# 48-17V_Buck_Converter.net
KiCad netlist of a schematic drawn in Altium Designer
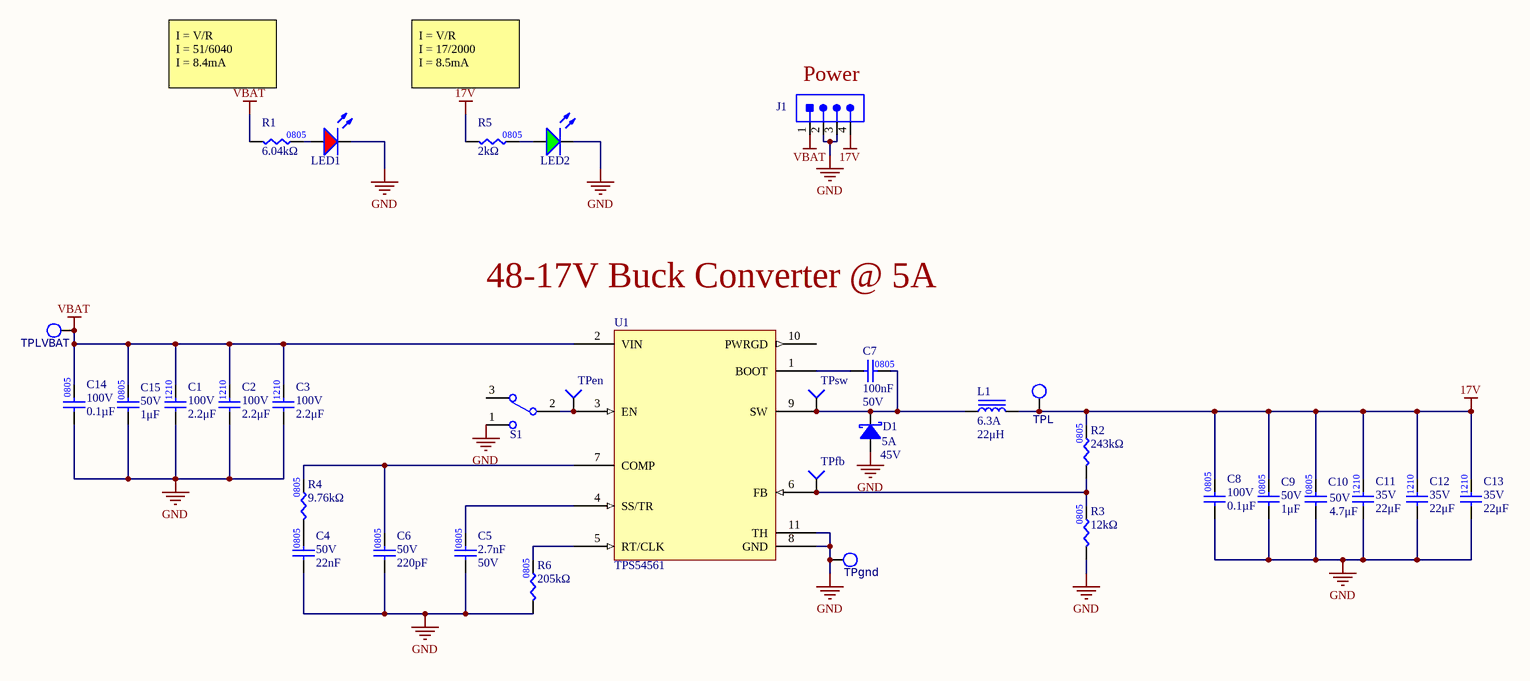
[diagram p0: 48-17V Buck Converter.SchDoc]

(export (version "E")
  (design (tool "Eeschema 10.0.6"))
  (components
    (comp (ref "C1")
      (value "2.2μF")
      (footprint "CAPC3225X270N")
      (description "CAP CER 2.2UF 100V X7R 1210")
      (fields (field (name "VOLTAGE RATING") "100V") (field (name "Comment") "CAP_2.2uF_100V_1210_1"))
      (libsource (lib "UWRT_Schematic_Library_2020") (part "CAP_2.2uF_100V_1210_1"))
    )
    (comp (ref "C2")
      (value "2.2μF")
      (footprint "CAPC3225X270N")
      (description "CAP CER 2.2UF 100V X7R 1210")
      (fields (field (name "VOLTAGE RATING") "100V") (field (name "Comment") "CAP_2.2uF_100V_1210_1"))
      (libsource (lib "UWRT_Schematic_Library_2020") (part "CAP_2.2uF_100V_1210_1"))
    )
    (comp (ref "C3")
      (value "2.2μF")
      (footprint "CAPC3225X270N")
      (description "CAP CER 2.2UF 100V X7R 1210")
      (fields (field (name "VOLTAGE RATING") "100V") (field (name "Comment") "CAP_2.2uF_100V_1210_1"))
      (libsource (lib "UWRT_Schematic_Library_2020") (part "CAP_2.2uF_100V_1210_1"))
    )
    (comp (ref "C4")
      (value "22nF")
      (footprint "CAP2012")
      (description "CAP CER 22nF 50V 0805")
      (fields (field (name "VOLTAGE RATING") "50V") (field (name "Comment") "CAP_22nF_50V_0805 +/- 1%"))
      (libsource (lib "UWRT_Schematic_Library_2020") (part "CAP_22nF_50V_0805 +/- 1%"))
    )
    (comp (ref "C5")
      (value "2.7nF")
      (footprint "CAP0805")
      (description "CAP CER 2700PF 50V C0G 0805")
      (fields (field (name "VOLTAGE RATING") "50V") (field (name "Comment") "CAP_2.7nF_50V_0805"))
      (libsource (lib "UWRT_Schematic_Library_2020") (part "CAP_2.7nF_50V_0805"))
    )
    (comp (ref "C6")
      (value "220pF")
      (footprint "CAP2012")
      (description "CAP CER 220pF 50V 0805 +/-1%")
      (fields (field (name "VOLTAGE RATING") "50V") (field (name "Comment") "CAP_220pF_50V_0805_2_1"))
      (libsource (lib "UWRT_Schematic_Library_2020") (part "CAP_220pF_50V_0805_2_1"))
    )
    (comp (ref "C7")
      (value "100nF")
      (footprint "CAP0805")
      (description "CAP CER 0.1UF 50V X7R 0805")
      (fields (field (name "VOLTAGE RATING") "50V") (field (name "Comment") "CAP_100nF_50V_0805"))
      (libsource (lib "UWRT_Schematic_Library_2020") (part "CAP_100nF_50V_0805"))
    )
    (comp (ref "C8")
      (value "0.1µF")
      (footprint "CAP0805")
      (description "CAP CER 0.1UF 100V X7R 0805")
      (fields (field (name "VOLTAGE RATING") "100V") (field (name "Comment") "CAP_0.1uF_100V_0805"))
      (libsource (lib "UWRT_Schematic_Library_2020") (part "CAP_0.1uF_100V_0805"))
    )
    (comp (ref "C9")
      (value "1μF")
      (footprint "CAP2012")
      (description "CAP CER 1UF 50V X7R 0805")
      (fields
        (field (name "LCSC PART #") "C28323")
        (field (name "VOLTAGE RATING") "50V")
        (field (name "Comment") "CAP_1uF_50V_0805")
      )
      (libsource (lib "UWRT_Schematic_Library_2020") (part "CAP_1uF_50V_0805"))
    )
    (comp (ref "C10")
      (value "4.7μF")
      (footprint "CAP0805")
      (description "CAP CER 4.7UF 50V X5R 0805")
      (fields
        (field (name "LCSC PART #") "C1779")
        (field (name "VOLTAGE RATING") "50V")
        (field (name "Comment") "CAP_4.7uF_50V_0805")
      )
      (libsource (lib "UWRT_Schematic_Library_2020") (part "CAP_4.7uF_50V_0805"))
    )
    (comp (ref "C11")
      (value "22μF")
      (footprint "CAP1210")
      (description "CAP CER 22UF 35V X5R 1210")
      (fields (field (name "VOLTAGE RATING") "35V") (field (name "Comment") "CAP_22uF_100V_1210"))
      (libsource (lib "UWRT_Schematic_Library_2020") (part "CAP_22uF_100V_1210"))
    )
    (comp (ref "C12")
      (value "22μF")
      (footprint "CAP1210")
      (description "CAP CER 22UF 35V X5R 1210")
      (fields (field (name "VOLTAGE RATING") "35V") (field (name "Comment") "CAP_22uF_100V_1210"))
      (libsource (lib "UWRT_Schematic_Library_2020") (part "CAP_22uF_100V_1210"))
    )
    (comp (ref "C13")
      (value "22μF")
      (footprint "CAP1210")
      (description "CAP CER 22UF 35V X5R 1210")
      (fields (field (name "VOLTAGE RATING") "35V") (field (name "Comment") "CAP_22uF_100V_1210"))
      (libsource (lib "UWRT_Schematic_Library_2020") (part "CAP_22uF_100V_1210"))
    )
    (comp (ref "C14")
      (value "0.1µF")
      (footprint "CAP0805")
      (description "CAP CER 0.1UF 100V X7R 0805")
      (fields (field (name "VOLTAGE RATING") "100V") (field (name "Comment") "CAP_0.1uF_100V_0805"))
      (libsource (lib "UWRT_Schematic_Library_2020") (part "CAP_0.1uF_100V_0805"))
    )
    (comp (ref "C15")
      (value "1μF")
      (footprint "CAP2012")
      (description "CAP CER 1UF 50V X7R 0805")
      (fields
        (field (name "LCSC PART #") "C28323")
        (field (name "VOLTAGE RATING") "50V")
        (field (name "Comment") "CAP_1uF_50V_0805")
      )
      (libsource (lib "UWRT_Schematic_Library_2020") (part "CAP_1uF_50V_0805"))
    )
    (comp (ref "D1")
      (value "~")
      (footprint "DIO_SCHOTTKY_45V_5A_vF480mV")
      (description "DIODE SCHOTTKY 45V 5A DO214AA")
      (fields (field (name "AVERAGE RECTIFIED CURRENT") "5A") (field (name "VR (MAX)") "45V"))
      (libsource (lib "UWRT_Schematic_Library_2020") (part "DIO_SCHOTTKY_45V_5A"))
    )
    (comp (ref "J1")
      (value "CON_2POS_SCREW_TERM")
      (footprint "MPT-04-01-01-L-RA-SD")
      (description "CONN HDR 4POS 5MM R/A SLDR")
      (libsource (lib "UWRT_Schematic_Library_2020") (part "CON_4POS_POWERBLADE_MALE"))
    )
    (comp (ref "L1")
      (value "IND_22uH_6.3A")
      (footprint "UWRT_Footprint_Library_2020:IND_22uH_6.3A")
      (description "FIXED IND 22UH 6.3A 25.7MOHM SMD")
      (fields (field (name "CURRENT RATING") "6.3A") (field (name "INDUCTANCE") "22μH"))
      (libsource (lib "UWRT_Schematic_Library_2020") (part "IND_22uH_6.3A"))
    )
    (comp (ref "LED1")
      (value "LED_RED")
      (footprint "LED_0805_RED")
      (description "LED RED DIFFUSED 0805 SMD")
      (libsource (lib "UWRT_Schematic_Library_2020") (part "LED_RED"))
    )
    (comp (ref "LED2")
      (value "LED_GREEN")
      (footprint "LED_0805_GREEN")
      (description "LED GREEN DIFFUSED 0805 SMD")
      (libsource (lib "UWRT_Schematic_Library_2020") (part "LED_GREEN"))
    )
    (comp (ref "R1")
      (value "6.04kΩ")
      (footprint "RES0805")
      (description "RES 6.04K OHM 1% 1/8W 0805")
      (fields (field (name "Comment") "RES_6.04kΩ_0805_1%"))
      (libsource (lib "UWRT_Schematic_Library_2020") (part "RES_6.04kΩ_0805_1%"))
    )
    (comp (ref "R2")
      (value "243kΩ")
      (footprint "RES0805")
      (description "RES 243K OHM 1% 1/8W 0805")
      (fields (field (name "Comment") "RES_243kΩ_0805_1%_1"))
      (libsource (lib "UWRT_Schematic_Library_2020") (part "RES_243kΩ_0805_1%_1"))
    )
    (comp (ref "R3")
      (value "12kΩ")
      (footprint "RES0805")
      (description "RES 12K OHM 1% 1/8W 0805")
      (fields (field (name "Comment") "RES_12kΩ_0805_1%"))
      (libsource (lib "UWRT_Schematic_Library_2020") (part "RES_12kΩ_0805_1%"))
    )
    (comp (ref "R4")
      (value "9.76kΩ")
      (footprint "RES0805")
      (description "RES 9.76K OHM 1% 1/8W 0805")
      (fields (field (name "Comment") "RES_9.76kΩ_0805_1%"))
      (libsource (lib "UWRT_Schematic_Library_2020") (part "RES_9.76kΩ_0805_1%"))
    )
    (comp (ref "R5")
      (value "2kΩ")
      (footprint "RES0805")
      (description "RES 2K OHM 1% 1/8W 0805")
      (fields (field (name "TOLERANCE") "1%") (field (name "Comment") "RES_2KΩ_0805_1%"))
      (libsource (lib "UWRT_Schematic_Library_2020") (part "RES_2KΩ_0805_1%"))
    )
    (comp (ref "R6")
      (value "205kΩ")
      (footprint "RES0805")
      (description "RES 205K OHM 1% 1/8W 0805")
      (fields (field (name "Comment") "RES_205kΩ_0805_1%"))
      (libsource (lib "UWRT_Schematic_Library_2020") (part "RES_205kΩ_0805_1%"))
    )
    (comp (ref "S1")
      (value "SW_SLIDE_TOGGLE")
      (footprint "UWRT_Footprint_Library_2020:SW_SLIDE_TOGGLE")
      (description "SWITCH SLIDE SPDT 200MA 30V")
      (libsource (lib "UWRT_Schematic_Library_2020") (part "SW_SLIDE_TOGGLE"))
    )
    (comp (ref "TPen")
      (value "TESTPOINT_1MM_CIRCLE")
      (footprint "TESTPOINT_CIRCLE_1MM")
      (description "TESTPOINT 1MM CIRCLE")
      (libsource (lib "UWRT_Schematic_Library_2020") (part "TESTPOINT_1MM_CIRCLE"))
    )
    (comp (ref "TPfb")
      (value "TESTPOINT_1MM_CIRCLE")
      (footprint "TESTPOINT_CIRCLE_1MM")
      (description "TESTPOINT 1MM CIRCLE")
      (libsource (lib "UWRT_Schematic_Library_2020") (part "TESTPOINT_1MM_CIRCLE"))
    )
    (comp (ref "TPgnd")
      (value "TESTPOINT_LOOP")
      (footprint "TESTPOINT_LOOP")
      (description "TESTPOINT THRUHOLE")
      (libsource (lib "UWRT_Schematic_Library_2020") (part "TESTPOINT_LOOP"))
    )
    (comp (ref "TPL")
      (value "TESTPOINT_LOOP")
      (footprint "TESTPOINT_LOOP")
      (description "TESTPOINT THRUHOLE")
      (libsource (lib "UWRT_Schematic_Library_2020") (part "TESTPOINT_LOOP"))
    )
    (comp (ref "TPLVBAT")
      (value "TESTPOINT_LOOP")
      (footprint "TESTPOINT_LOOP")
      (description "TESTPOINT THRUHOLE")
      (libsource (lib "UWRT_Schematic_Library_2020") (part "TESTPOINT_LOOP"))
    )
    (comp (ref "TPsw")
      (value "TESTPOINT_1MM_CIRCLE")
      (footprint "TESTPOINT_CIRCLE_1MM")
      (description "TESTPOINT 1MM CIRCLE")
      (libsource (lib "UWRT_Schematic_Library_2020") (part "TESTPOINT_1MM_CIRCLE"))
    )
    (comp (ref "U1")
      (value "TPS54561")
      (footprint "BUCK_TPS54561DPRR")
      (description "Buck Switching Regulator IC Positive Adjustable 0.8V 1 Output 5A 10-WDFN Exposed Pad")
      (libsource (lib "UWRT_Schematic_Library_2020") (part "TPS54561"))
    )
  )
  (nets
    (net (code "1") (name "17V") (class "Default")
      (node (ref "C10") (pin "2") (pinfunction "2_2") (pintype "passive"))
      (node (ref "C11") (pin "2") (pinfunction "2_2") (pintype "passive"))
      (node (ref "C12") (pin "2") (pinfunction "2_2") (pintype "passive"))
      (node (ref "C13") (pin "2") (pinfunction "2_2") (pintype "passive"))
      (node (ref "C8") (pin "2") (pinfunction "2_2") (pintype "passive"))
      (node (ref "C9") (pin "2") (pinfunction "2_2") (pintype "passive"))
      (node (ref "J1") (pin "4") (pinfunction "2_4") (pintype "passive"))
      (node (ref "L1") (pin "2") (pinfunction "2_2") (pintype "passive"))
      (node (ref "R2") (pin "2") (pinfunction "2_2") (pintype "passive"))
      (node (ref "R5") (pin "1") (pinfunction "1_1") (pintype "passive"))
      (node (ref "TPL") (pin "1") (pintype "passive"))
    )
    (net (code "2") (name "GND") (class "Default")
      (node (ref "C1") (pin "1") (pinfunction "1_1") (pintype "passive"))
      (node (ref "C10") (pin "1") (pinfunction "1_1") (pintype "passive"))
      (node (ref "C11") (pin "1") (pinfunction "1_1") (pintype "passive"))
      (node (ref "C12") (pin "1") (pinfunction "1_1") (pintype "passive"))
      (node (ref "C13") (pin "1") (pinfunction "1_1") (pintype "passive"))
      (node (ref "C14") (pin "1") (pinfunction "1_1") (pintype "passive"))
      (node (ref "C15") (pin "1") (pinfunction "1_1") (pintype "passive"))
      (node (ref "C2") (pin "1") (pinfunction "1_1") (pintype "passive"))
      (node (ref "C3") (pin "1") (pinfunction "1_1") (pintype "passive"))
      (node (ref "C4") (pin "1") (pinfunction "1_1") (pintype "passive"))
      (node (ref "C5") (pin "1") (pinfunction "1_1") (pintype "passive"))
      (node (ref "C6") (pin "1") (pinfunction "1_1") (pintype "passive"))
      (node (ref "C8") (pin "1") (pinfunction "1_1") (pintype "passive"))
      (node (ref "C9") (pin "1") (pinfunction "1_1") (pintype "passive"))
      (node (ref "D1") (pin "1") (pinfunction "Anode_1") (pintype "passive"))
      (node (ref "J1") (pin "2") (pinfunction "2_2") (pintype "passive"))
      (node (ref "J1") (pin "3") (pinfunction "1_3") (pintype "passive"))
      (node (ref "LED1") (pin "2") (pinfunction "K_2") (pintype "passive"))
      (node (ref "LED2") (pin "2") (pinfunction "K_2") (pintype "passive"))
      (node (ref "R3") (pin "1") (pinfunction "1_1") (pintype "passive"))
      (node (ref "R6") (pin "1") (pinfunction "1_1") (pintype "passive"))
      (node (ref "S1") (pin "1") (pinfunction "1_1") (pintype "passive"))
      (node (ref "TPgnd") (pin "1") (pintype "passive"))
      (node (ref "U1") (pin "11") (pinfunction "TH_11") (pintype "power_in"))
      (node (ref "U1") (pin "8") (pinfunction "GND_8") (pintype "power_in"))
    )
    (net (code "3") (name "Net-(C4-Pad2)") (class "Default")
      (node (ref "C4") (pin "2") (pinfunction "2_2") (pintype "passive"))
      (node (ref "R4") (pin "1") (pinfunction "1_1") (pintype "passive"))
    )
    (net (code "4") (name "Net-(D1-Cathode)") (class "Default")
      (node (ref "C7") (pin "2") (pinfunction "2_2") (pintype "passive"))
      (node (ref "D1") (pin "2") (pinfunction "Cathode_2") (pintype "passive"))
      (node (ref "L1") (pin "1") (pinfunction "1_1") (pintype "passive"))
      (node (ref "TPsw") (pin "1") (pinfunction "=value_1") (pintype "passive"))
      (node (ref "U1") (pin "9") (pinfunction "SW_9") (pintype "power_in"))
    )
    (net (code "5") (name "Net-(LED1-A)") (class "Default")
      (node (ref "LED1") (pin "1") (pinfunction "A_1") (pintype "passive"))
      (node (ref "R1") (pin "2") (pinfunction "2_2") (pintype "passive"))
    )
    (net (code "6") (name "Net-(LED2-A)") (class "Default")
      (node (ref "LED2") (pin "1") (pinfunction "A_1") (pintype "passive"))
      (node (ref "R5") (pin "2") (pinfunction "2_2") (pintype "passive"))
    )
    (net (code "7") (name "Net-(TPen-=value)") (class "Default")
      (node (ref "S1") (pin "2") (pinfunction "2_2") (pintype "passive"))
      (node (ref "TPen") (pin "1") (pinfunction "=value_1") (pintype "passive"))
      (node (ref "U1") (pin "3") (pinfunction "EN_3") (pintype "input"))
    )
    (net (code "8") (name "Net-(TPfb-=value)") (class "Default")
      (node (ref "R2") (pin "1") (pinfunction "1_1") (pintype "passive"))
      (node (ref "R3") (pin "2") (pinfunction "2_2") (pintype "passive"))
      (node (ref "TPfb") (pin "1") (pinfunction "=value_1") (pintype "passive"))
      (node (ref "U1") (pin "6") (pinfunction "FB_6") (pintype "input"))
    )
    (net (code "9") (name "Net-(U1-BOOT)") (class "Default")
      (node (ref "C7") (pin "1") (pinfunction "1_1") (pintype "passive"))
      (node (ref "U1") (pin "1") (pinfunction "BOOT_1") (pintype "power_in"))
    )
    (net (code "10") (name "Net-(U1-COMP)") (class "Default")
      (node (ref "C6") (pin "2") (pinfunction "2_2") (pintype "passive"))
      (node (ref "R4") (pin "2") (pinfunction "2_2") (pintype "passive"))
      (node (ref "U1") (pin "7") (pinfunction "COMP_7") (pintype "power_in"))
    )
    (net (code "11") (name "Net-(U1-RT{slash}CLK)") (class "Default")
      (node (ref "R6") (pin "2") (pinfunction "2_2") (pintype "passive"))
      (node (ref "U1") (pin "5") (pinfunction "RT/CLK_5") (pintype "input"))
    )
    (net (code "12") (name "Net-(U1-SS{slash}TR)") (class "Default")
      (node (ref "C5") (pin "2") (pinfunction "2_2") (pintype "passive"))
      (node (ref "U1") (pin "4") (pinfunction "SS/TR_4") (pintype "input"))
    )
    (net (code "13") (name "VBAT") (class "Default")
      (node (ref "C1") (pin "2") (pinfunction "2_2") (pintype "passive"))
      (node (ref "C14") (pin "2") (pinfunction "2_2") (pintype "passive"))
      (node (ref "C15") (pin "2") (pinfunction "2_2") (pintype "passive"))
      (node (ref "C2") (pin "2") (pinfunction "2_2") (pintype "passive"))
      (node (ref "C3") (pin "2") (pinfunction "2_2") (pintype "passive"))
      (node (ref "J1") (pin "1") (pinfunction "1_1") (pintype "passive"))
      (node (ref "R1") (pin "1") (pinfunction "1_1") (pintype "passive"))
      (node (ref "TPLVBAT") (pin "1") (pintype "passive"))
      (node (ref "U1") (pin "2") (pinfunction "VIN_2") (pintype "power_in"))
    )
    (net (code "14") (name "unconnected-(S1-Pad3)") (class "Default")
      (node (ref "S1") (pin "3") (pinfunction "3_3") (pintype "passive"))
    )
    (net (code "15") (name "unconnected-(U1-PWRGD-Pad10)") (class "Default")
      (node (ref "U1") (pin "10") (pinfunction "PWRGD_10") (pintype "output"))
    )
  )
)
